# AVRI2CIO.net
KiCad netlist of a schematic drawn in EAGLE
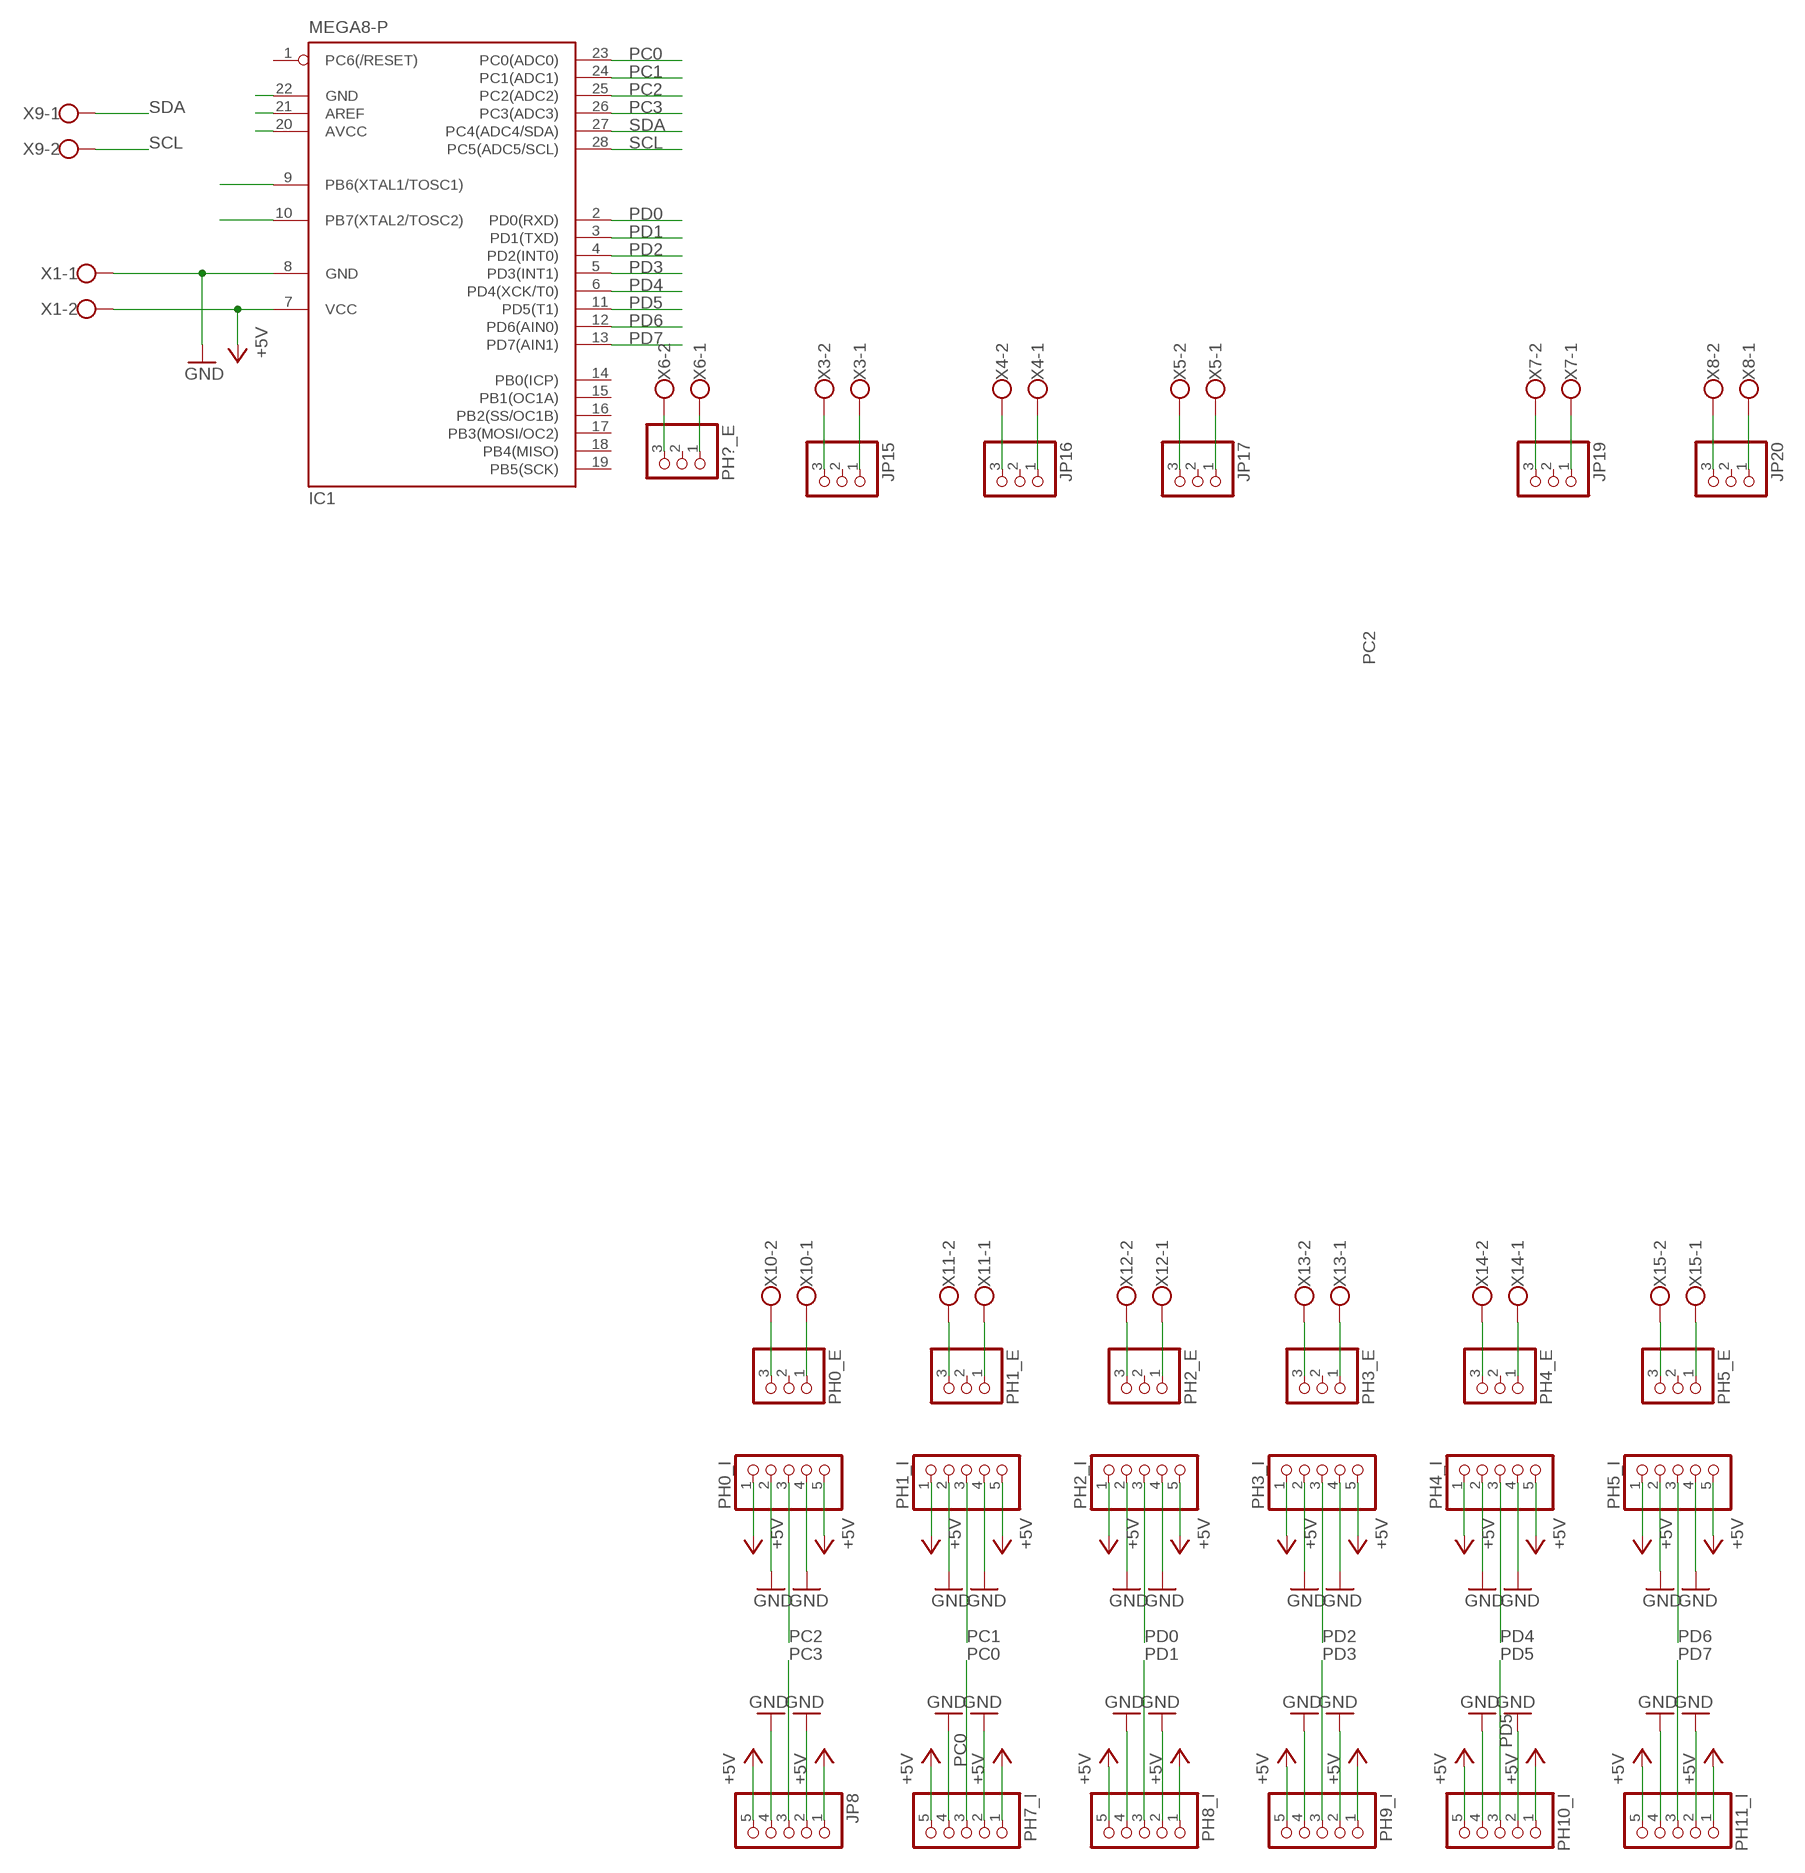
[diagram p0: schematic, sheet 1]

(export (version "E")
  (design (tool "Eeschema 10.0.6"))
  (components
    (comp (ref "IC1")
      (value "MEGA8-P")
      (footprint "eagle-import:DIL28-3")
      (libsource (lib "eagle-import") (part "MEGA8-P"))
    )
    (comp (ref "JP8")
      (value "PINHD-1X5")
      (footprint "eagle-import:1X05")
      (libsource (lib "eagle-import") (part "PINHD-1X5"))
    )
    (comp (ref "JP15")
      (value "PINHD-1X3")
      (footprint "eagle-import:1X03")
      (libsource (lib "eagle-import") (part "PINHD-1X3"))
    )
    (comp (ref "JP16")
      (value "PINHD-1X3")
      (footprint "eagle-import:1X03")
      (libsource (lib "eagle-import") (part "PINHD-1X3"))
    )
    (comp (ref "JP17")
      (value "PINHD-1X3")
      (footprint "eagle-import:1X03")
      (libsource (lib "eagle-import") (part "PINHD-1X3"))
    )
    (comp (ref "JP19")
      (value "PINHD-1X3")
      (footprint "eagle-import:1X03")
      (libsource (lib "eagle-import") (part "PINHD-1X3"))
    )
    (comp (ref "JP20")
      (value "PINHD-1X3")
      (footprint "eagle-import:1X03")
      (libsource (lib "eagle-import") (part "PINHD-1X3"))
    )
    (comp (ref "PH0_E")
      (value "PINHD-1X3")
      (footprint "eagle-import:1X03")
      (libsource (lib "eagle-import") (part "PINHD-1X3"))
    )
    (comp (ref "PH0_I")
      (value "PINHD-1X5")
      (footprint "eagle-import:1X05")
      (libsource (lib "eagle-import") (part "PINHD-1X5"))
    )
    (comp (ref "PH1_E")
      (value "PINHD-1X3")
      (footprint "eagle-import:1X03")
      (libsource (lib "eagle-import") (part "PINHD-1X3"))
    )
    (comp (ref "PH1_I")
      (value "PINHD-1X5")
      (footprint "eagle-import:1X05")
      (libsource (lib "eagle-import") (part "PINHD-1X5"))
    )
    (comp (ref "PH2_E")
      (value "PINHD-1X3")
      (footprint "eagle-import:1X03")
      (libsource (lib "eagle-import") (part "PINHD-1X3"))
    )
    (comp (ref "PH2_I")
      (value "PINHD-1X5")
      (footprint "eagle-import:1X05")
      (libsource (lib "eagle-import") (part "PINHD-1X5"))
    )
    (comp (ref "PH3_E")
      (value "PINHD-1X3")
      (footprint "eagle-import:1X03")
      (libsource (lib "eagle-import") (part "PINHD-1X3"))
    )
    (comp (ref "PH3_I")
      (value "PINHD-1X5")
      (footprint "eagle-import:1X05")
      (libsource (lib "eagle-import") (part "PINHD-1X5"))
    )
    (comp (ref "PH4_E")
      (value "PINHD-1X3")
      (footprint "eagle-import:1X03")
      (libsource (lib "eagle-import") (part "PINHD-1X3"))
    )
    (comp (ref "PH4_I")
      (value "PINHD-1X5")
      (footprint "eagle-import:1X05")
      (libsource (lib "eagle-import") (part "PINHD-1X5"))
    )
    (comp (ref "PH5_E")
      (value "PINHD-1X3")
      (footprint "eagle-import:1X03")
      (libsource (lib "eagle-import") (part "PINHD-1X3"))
    )
    (comp (ref "PH5_I")
      (value "PINHD-1X5")
      (footprint "eagle-import:1X05")
      (libsource (lib "eagle-import") (part "PINHD-1X5"))
    )
    (comp (ref "PH7_I")
      (value "PINHD-1X5")
      (footprint "eagle-import:1X05")
      (libsource (lib "eagle-import") (part "PINHD-1X5"))
    )
    (comp (ref "PH8_I")
      (value "PINHD-1X5")
      (footprint "eagle-import:1X05")
      (libsource (lib "eagle-import") (part "PINHD-1X5"))
    )
    (comp (ref "PH9_I")
      (value "PINHD-1X5")
      (footprint "eagle-import:1X05")
      (libsource (lib "eagle-import") (part "PINHD-1X5"))
    )
    (comp (ref "PH10_I")
      (value "PINHD-1X5")
      (footprint "eagle-import:1X05")
      (libsource (lib "eagle-import") (part "PINHD-1X5"))
    )
    (comp (ref "PH11_I")
      (value "PINHD-1X5")
      (footprint "eagle-import:1X05")
      (libsource (lib "eagle-import") (part "PINHD-1X5"))
    )
    (comp (ref "PH?_E")
      (value "PINHD-1X3")
      (footprint "eagle-import:1X03")
      (libsource (lib "eagle-import") (part "PINHD-1X3"))
    )
    (comp (ref "X1")
      (value "W237-102")
      (footprint "eagle-import:W237-102")
      (fields (field (name "MPN") "237-102"))
      (libsource (lib "eagle-import") (part "W237-102"))
    )
    (comp (ref "X3")
      (value "W237-102")
      (footprint "eagle-import:W237-102")
      (fields (field (name "MPN") "237-102"))
      (libsource (lib "eagle-import") (part "W237-102"))
    )
    (comp (ref "X4")
      (value "W237-102")
      (footprint "eagle-import:W237-102")
      (fields (field (name "MPN") "237-102"))
      (libsource (lib "eagle-import") (part "W237-102"))
    )
    (comp (ref "X5")
      (value "W237-102")
      (footprint "eagle-import:W237-102")
      (fields (field (name "MPN") "237-102"))
      (libsource (lib "eagle-import") (part "W237-102"))
    )
    (comp (ref "X6")
      (value "W237-102")
      (footprint "eagle-import:W237-102")
      (fields (field (name "MPN") "237-102"))
      (libsource (lib "eagle-import") (part "W237-102"))
    )
    (comp (ref "X7")
      (value "W237-102")
      (footprint "eagle-import:W237-102")
      (fields (field (name "MPN") "237-102"))
      (libsource (lib "eagle-import") (part "W237-102"))
    )
    (comp (ref "X8")
      (value "W237-102")
      (footprint "eagle-import:W237-102")
      (fields (field (name "MPN") "237-102"))
      (libsource (lib "eagle-import") (part "W237-102"))
    )
    (comp (ref "X9")
      (value "W237-102")
      (footprint "eagle-import:W237-102")
      (fields (field (name "MPN") "237-102"))
      (libsource (lib "eagle-import") (part "W237-102"))
    )
    (comp (ref "X10")
      (value "W237-102")
      (footprint "eagle-import:W237-102")
      (fields (field (name "MPN") "237-102"))
      (libsource (lib "eagle-import") (part "W237-102"))
    )
    (comp (ref "X11")
      (value "W237-102")
      (footprint "eagle-import:W237-102")
      (fields (field (name "MPN") "237-102"))
      (libsource (lib "eagle-import") (part "W237-102"))
    )
    (comp (ref "X12")
      (value "W237-102")
      (footprint "eagle-import:W237-102")
      (fields (field (name "MPN") "237-102"))
      (libsource (lib "eagle-import") (part "W237-102"))
    )
    (comp (ref "X13")
      (value "W237-102")
      (footprint "eagle-import:W237-102")
      (fields (field (name "MPN") "237-102"))
      (libsource (lib "eagle-import") (part "W237-102"))
    )
    (comp (ref "X14")
      (value "W237-102")
      (footprint "eagle-import:W237-102")
      (fields (field (name "MPN") "237-102"))
      (libsource (lib "eagle-import") (part "W237-102"))
    )
    (comp (ref "X15")
      (value "W237-102")
      (footprint "eagle-import:W237-102")
      (fields (field (name "MPN") "237-102"))
      (libsource (lib "eagle-import") (part "W237-102"))
    )
  )
  (nets
    (net (code "1") (name "+5V") (class "Default")
      (node (ref "IC1") (pin "7") (pinfunction "VCC_7") (pintype "power_in"))
      (node (ref "JP8") (pin "1") (pinfunction "1_1") (pintype "passive"))
      (node (ref "JP8") (pin "5") (pinfunction "5_5") (pintype "passive"))
      (node (ref "PH0_I") (pin "1") (pinfunction "1_1") (pintype "passive"))
      (node (ref "PH0_I") (pin "5") (pinfunction "5_5") (pintype "passive"))
      (node (ref "PH10_I") (pin "1") (pinfunction "1_1") (pintype "passive"))
      (node (ref "PH10_I") (pin "5") (pinfunction "5_5") (pintype "passive"))
      (node (ref "PH11_I") (pin "1") (pinfunction "1_1") (pintype "passive"))
      (node (ref "PH11_I") (pin "5") (pinfunction "5_5") (pintype "passive"))
      (node (ref "PH1_I") (pin "1") (pinfunction "1_1") (pintype "passive"))
      (node (ref "PH1_I") (pin "5") (pinfunction "5_5") (pintype "passive"))
      (node (ref "PH2_I") (pin "1") (pinfunction "1_1") (pintype "passive"))
      (node (ref "PH2_I") (pin "5") (pinfunction "5_5") (pintype "passive"))
      (node (ref "PH3_I") (pin "1") (pinfunction "1_1") (pintype "passive"))
      (node (ref "PH3_I") (pin "5") (pinfunction "5_5") (pintype "passive"))
      (node (ref "PH4_I") (pin "1") (pinfunction "1_1") (pintype "passive"))
      (node (ref "PH4_I") (pin "5") (pinfunction "5_5") (pintype "passive"))
      (node (ref "PH5_I") (pin "1") (pinfunction "1_1") (pintype "passive"))
      (node (ref "PH5_I") (pin "5") (pinfunction "5_5") (pintype "passive"))
      (node (ref "PH7_I") (pin "1") (pinfunction "1_1") (pintype "passive"))
      (node (ref "PH7_I") (pin "5") (pinfunction "5_5") (pintype "passive"))
      (node (ref "PH8_I") (pin "1") (pinfunction "1_1") (pintype "passive"))
      (node (ref "PH8_I") (pin "5") (pinfunction "5_5") (pintype "passive"))
      (node (ref "PH9_I") (pin "1") (pinfunction "1_1") (pintype "passive"))
      (node (ref "PH9_I") (pin "5") (pinfunction "5_5") (pintype "passive"))
      (node (ref "X1") (pin "2") (pinfunction "KL_2") (pintype "passive"))
    )
    (net (code "2") (name "/PC0") (class "Default")
      (node (ref "IC1") (pin "23") (pinfunction "PC0(ADC0)_23") (pintype "bidirectional"))
      (node (ref "PH7_I") (pin "3") (pinfunction "3_3") (pintype "passive"))
    )
    (net (code "3") (name "/PC1") (class "Default")
      (node (ref "IC1") (pin "24") (pinfunction "PC1(ADC1)_24") (pintype "bidirectional"))
      (node (ref "PH1_I") (pin "3") (pinfunction "3_3") (pintype "passive"))
    )
    (net (code "4") (name "/PC2") (class "Default")
      (node (ref "IC1") (pin "25") (pinfunction "PC2(ADC2)_25") (pintype "bidirectional"))
      (node (ref "PH0_I") (pin "3") (pinfunction "3_3") (pintype "passive"))
    )
    (net (code "5") (name "/PC3") (class "Default")
      (node (ref "IC1") (pin "26") (pinfunction "PC3(ADC3)_26") (pintype "bidirectional"))
      (node (ref "JP8") (pin "3") (pinfunction "3_3") (pintype "passive"))
    )
    (net (code "6") (name "/PD0") (class "Default")
      (node (ref "IC1") (pin "2") (pinfunction "PD0(RXD)_2") (pintype "bidirectional"))
      (node (ref "PH2_I") (pin "3") (pinfunction "3_3") (pintype "passive"))
    )
    (net (code "7") (name "/PD1") (class "Default")
      (node (ref "IC1") (pin "3") (pinfunction "PD1(TXD)_3") (pintype "bidirectional"))
      (node (ref "PH8_I") (pin "3") (pinfunction "3_3") (pintype "passive"))
    )
    (net (code "8") (name "/PD2") (class "Default")
      (node (ref "IC1") (pin "4") (pinfunction "PD2(INT0)_4") (pintype "bidirectional"))
      (node (ref "PH3_I") (pin "3") (pinfunction "3_3") (pintype "passive"))
    )
    (net (code "9") (name "/PD3") (class "Default")
      (node (ref "IC1") (pin "5") (pinfunction "PD3(INT1)_5") (pintype "bidirectional"))
      (node (ref "PH9_I") (pin "3") (pinfunction "3_3") (pintype "passive"))
    )
    (net (code "10") (name "/PD4") (class "Default")
      (node (ref "IC1") (pin "6") (pinfunction "PD4(XCK/T0)_6") (pintype "bidirectional"))
      (node (ref "PH4_I") (pin "3") (pinfunction "3_3") (pintype "passive"))
    )
    (net (code "11") (name "/PD5") (class "Default")
      (node (ref "IC1") (pin "11") (pinfunction "PD5(T1)_11") (pintype "bidirectional"))
      (node (ref "PH10_I") (pin "3") (pinfunction "3_3") (pintype "passive"))
    )
    (net (code "12") (name "/PD6") (class "Default")
      (node (ref "IC1") (pin "12") (pinfunction "PD6(AIN0)_12") (pintype "bidirectional"))
      (node (ref "PH5_I") (pin "3") (pinfunction "3_3") (pintype "passive"))
    )
    (net (code "13") (name "/PD7") (class "Default")
      (node (ref "IC1") (pin "13") (pinfunction "PD7(AIN1)_13") (pintype "bidirectional"))
      (node (ref "PH11_I") (pin "3") (pinfunction "3_3") (pintype "passive"))
    )
    (net (code "14") (name "/SCL") (class "Default")
      (node (ref "IC1") (pin "28") (pinfunction "PC5(ADC5/SCL)_28") (pintype "bidirectional"))
      (node (ref "X9") (pin "2") (pinfunction "KL_2") (pintype "passive"))
    )
    (net (code "15") (name "/SDA") (class "Default")
      (node (ref "IC1") (pin "27") (pinfunction "PC4(ADC4/SDA)_27") (pintype "bidirectional"))
      (node (ref "X9") (pin "1") (pinfunction "KL_1") (pintype "passive"))
    )
    (net (code "16") (name "GND") (class "Default")
      (node (ref "IC1") (pin "8") (pinfunction "GND_8") (pintype "power_in"))
      (node (ref "JP8") (pin "2") (pinfunction "2_2") (pintype "passive"))
      (node (ref "JP8") (pin "4") (pinfunction "4_4") (pintype "passive"))
      (node (ref "PH0_I") (pin "2") (pinfunction "2_2") (pintype "passive"))
      (node (ref "PH0_I") (pin "4") (pinfunction "4_4") (pintype "passive"))
      (node (ref "PH10_I") (pin "2") (pinfunction "2_2") (pintype "passive"))
      (node (ref "PH10_I") (pin "4") (pinfunction "4_4") (pintype "passive"))
      (node (ref "PH11_I") (pin "2") (pinfunction "2_2") (pintype "passive"))
      (node (ref "PH11_I") (pin "4") (pinfunction "4_4") (pintype "passive"))
      (node (ref "PH1_I") (pin "2") (pinfunction "2_2") (pintype "passive"))
      (node (ref "PH1_I") (pin "4") (pinfunction "4_4") (pintype "passive"))
      (node (ref "PH2_I") (pin "2") (pinfunction "2_2") (pintype "passive"))
      (node (ref "PH2_I") (pin "4") (pinfunction "4_4") (pintype "passive"))
      (node (ref "PH3_I") (pin "2") (pinfunction "2_2") (pintype "passive"))
      (node (ref "PH3_I") (pin "4") (pinfunction "4_4") (pintype "passive"))
      (node (ref "PH4_I") (pin "2") (pinfunction "2_2") (pintype "passive"))
      (node (ref "PH4_I") (pin "4") (pinfunction "4_4") (pintype "passive"))
      (node (ref "PH5_I") (pin "2") (pinfunction "2_2") (pintype "passive"))
      (node (ref "PH5_I") (pin "4") (pinfunction "4_4") (pintype "passive"))
      (node (ref "PH7_I") (pin "2") (pinfunction "2_2") (pintype "passive"))
      (node (ref "PH7_I") (pin "4") (pinfunction "4_4") (pintype "passive"))
      (node (ref "PH8_I") (pin "2") (pinfunction "2_2") (pintype "passive"))
      (node (ref "PH8_I") (pin "4") (pinfunction "4_4") (pintype "passive"))
      (node (ref "PH9_I") (pin "2") (pinfunction "2_2") (pintype "passive"))
      (node (ref "PH9_I") (pin "4") (pinfunction "4_4") (pintype "passive"))
      (node (ref "X1") (pin "1") (pinfunction "KL_1") (pintype "passive"))
    )
    (net (code "17") (name "Net-(X3A-KL)") (class "Default")
      (node (ref "JP15") (pin "1") (pinfunction "1_1") (pintype "passive"))
      (node (ref "X3") (pin "1") (pinfunction "KL_1") (pintype "passive"))
    )
    (net (code "18") (name "Net-(X3B-KL)") (class "Default")
      (node (ref "JP15") (pin "3") (pinfunction "3_3") (pintype "passive"))
      (node (ref "X3") (pin "2") (pinfunction "KL_2") (pintype "passive"))
    )
    (net (code "19") (name "Net-(X4A-KL)") (class "Default")
      (node (ref "JP16") (pin "1") (pinfunction "1_1") (pintype "passive"))
      (node (ref "X4") (pin "1") (pinfunction "KL_1") (pintype "passive"))
    )
    (net (code "20") (name "Net-(X4B-KL)") (class "Default")
      (node (ref "JP16") (pin "3") (pinfunction "3_3") (pintype "passive"))
      (node (ref "X4") (pin "2") (pinfunction "KL_2") (pintype "passive"))
    )
    (net (code "21") (name "Net-(X5A-KL)") (class "Default")
      (node (ref "JP17") (pin "1") (pinfunction "1_1") (pintype "passive"))
      (node (ref "X5") (pin "1") (pinfunction "KL_1") (pintype "passive"))
    )
    (net (code "22") (name "Net-(X5B-KL)") (class "Default")
      (node (ref "JP17") (pin "3") (pinfunction "3_3") (pintype "passive"))
      (node (ref "X5") (pin "2") (pinfunction "KL_2") (pintype "passive"))
    )
    (net (code "23") (name "Net-(X6A-KL)") (class "Default")
      (node (ref "PH?_E") (pin "1") (pinfunction "1_1") (pintype "passive"))
      (node (ref "X6") (pin "1") (pinfunction "KL_1") (pintype "passive"))
    )
    (net (code "24") (name "Net-(X6B-KL)") (class "Default")
      (node (ref "PH?_E") (pin "3") (pinfunction "3_3") (pintype "passive"))
      (node (ref "X6") (pin "2") (pinfunction "KL_2") (pintype "passive"))
    )
    (net (code "25") (name "Net-(X7A-KL)") (class "Default")
      (node (ref "JP19") (pin "1") (pinfunction "1_1") (pintype "passive"))
      (node (ref "X7") (pin "1") (pinfunction "KL_1") (pintype "passive"))
    )
    (net (code "26") (name "Net-(X7B-KL)") (class "Default")
      (node (ref "JP19") (pin "3") (pinfunction "3_3") (pintype "passive"))
      (node (ref "X7") (pin "2") (pinfunction "KL_2") (pintype "passive"))
    )
    (net (code "27") (name "Net-(X8A-KL)") (class "Default")
      (node (ref "JP20") (pin "1") (pinfunction "1_1") (pintype "passive"))
      (node (ref "X8") (pin "1") (pinfunction "KL_1") (pintype "passive"))
    )
    (net (code "28") (name "Net-(X8B-KL)") (class "Default")
      (node (ref "JP20") (pin "3") (pinfunction "3_3") (pintype "passive"))
      (node (ref "X8") (pin "2") (pinfunction "KL_2") (pintype "passive"))
    )
    (net (code "29") (name "Net-(X10A-KL)") (class "Default")
      (node (ref "PH0_E") (pin "1") (pinfunction "1_1") (pintype "passive"))
      (node (ref "X10") (pin "1") (pinfunction "KL_1") (pintype "passive"))
    )
    (net (code "30") (name "Net-(X10B-KL)") (class "Default")
      (node (ref "PH0_E") (pin "3") (pinfunction "3_3") (pintype "passive"))
      (node (ref "X10") (pin "2") (pinfunction "KL_2") (pintype "passive"))
    )
    (net (code "31") (name "Net-(X11A-KL)") (class "Default")
      (node (ref "PH1_E") (pin "1") (pinfunction "1_1") (pintype "passive"))
      (node (ref "X11") (pin "1") (pinfunction "KL_1") (pintype "passive"))
    )
    (net (code "32") (name "Net-(X11B-KL)") (class "Default")
      (node (ref "PH1_E") (pin "3") (pinfunction "3_3") (pintype "passive"))
      (node (ref "X11") (pin "2") (pinfunction "KL_2") (pintype "passive"))
    )
    (net (code "33") (name "Net-(X12A-KL)") (class "Default")
      (node (ref "PH2_E") (pin "1") (pinfunction "1_1") (pintype "passive"))
      (node (ref "X12") (pin "1") (pinfunction "KL_1") (pintype "passive"))
    )
    (net (code "34") (name "Net-(X12B-KL)") (class "Default")
      (node (ref "PH2_E") (pin "3") (pinfunction "3_3") (pintype "passive"))
      (node (ref "X12") (pin "2") (pinfunction "KL_2") (pintype "passive"))
    )
    (net (code "35") (name "Net-(X13A-KL)") (class "Default")
      (node (ref "PH3_E") (pin "1") (pinfunction "1_1") (pintype "passive"))
      (node (ref "X13") (pin "1") (pinfunction "KL_1") (pintype "passive"))
    )
    (net (code "36") (name "Net-(X13B-KL)") (class "Default")
      (node (ref "PH3_E") (pin "3") (pinfunction "3_3") (pintype "passive"))
      (node (ref "X13") (pin "2") (pinfunction "KL_2") (pintype "passive"))
    )
    (net (code "37") (name "Net-(X14A-KL)") (class "Default")
      (node (ref "PH4_E") (pin "1") (pinfunction "1_1") (pintype "passive"))
      (node (ref "X14") (pin "1") (pinfunction "KL_1") (pintype "passive"))
    )
    (net (code "38") (name "Net-(X14B-KL)") (class "Default")
      (node (ref "PH4_E") (pin "3") (pinfunction "3_3") (pintype "passive"))
      (node (ref "X14") (pin "2") (pinfunction "KL_2") (pintype "passive"))
    )
    (net (code "39") (name "Net-(X15A-KL)") (class "Default")
      (node (ref "PH5_E") (pin "1") (pinfunction "1_1") (pintype "passive"))
      (node (ref "X15") (pin "1") (pinfunction "KL_1") (pintype "passive"))
    )
    (net (code "40") (name "Net-(X15B-KL)") (class "Default")
      (node (ref "PH5_E") (pin "3") (pinfunction "3_3") (pintype "passive"))
      (node (ref "X15") (pin "2") (pinfunction "KL_2") (pintype "passive"))
    )
    (net (code "41") (name "unconnected-(IC1-AREF-Pad21)") (class "Default")
      (node (ref "IC1") (pin "21") (pinfunction "AREF_21") (pintype "passive"))
    )
    (net (code "42") (name "unconnected-(IC1-AVCC-Pad20)") (class "Default")
      (node (ref "IC1") (pin "20") (pinfunction "AVCC_20") (pintype "power_in"))
    )
    (net (code "43") (name "unconnected-(IC1-GND-Pad22)") (class "Default")
      (node (ref "IC1") (pin "22") (pinfunction "GND_22") (pintype "power_in"))
    )
    (net (code "44") (name "unconnected-(IC1-PB0(ICP)-Pad14)") (class "Default")
      (node (ref "IC1") (pin "14") (pinfunction "PB0(ICP)_14") (pintype "bidirectional"))
    )
    (net (code "45") (name "unconnected-(IC1-PB1(OC1A)-Pad15)") (class "Default")
      (node (ref "IC1") (pin "15") (pinfunction "PB1(OC1A)_15") (pintype "bidirectional"))
    )
    (net (code "46") (name "unconnected-(IC1-PB2(SS{slash}OC1B)-Pad16)") (class "Default")
      (node (ref "IC1") (pin "16") (pinfunction "PB2(SS/OC1B)_16") (pintype "bidirectional"))
    )
    (net (code "47") (name "unconnected-(IC1-PB3(MOSI{slash}OC2)-Pad17)") (class "Default")
      (node (ref "IC1") (pin "17") (pinfunction "PB3(MOSI/OC2)_17") (pintype "bidirectional"))
    )
    (net (code "48") (name "unconnected-(IC1-PB4(MISO)-Pad18)") (class "Default")
      (node (ref "IC1") (pin "18") (pinfunction "PB4(MISO)_18") (pintype "bidirectional"))
    )
    (net (code "49") (name "unconnected-(IC1-PB5(SCK)-Pad19)") (class "Default")
      (node (ref "IC1") (pin "19") (pinfunction "PB5(SCK)_19") (pintype "bidirectional"))
    )
    (net (code "50") (name "unconnected-(IC1-PB6(XTAL1{slash}TOSC1)-Pad9)") (class "Default")
      (node (ref "IC1") (pin "9") (pinfunction "PB6(XTAL1/TOSC1)_9") (pintype "bidirectional"))
    )
    (net (code "51") (name "unconnected-(IC1-PB7(XTAL2{slash}TOSC2)-Pad10)") (class "Default")
      (node (ref "IC1") (pin "10") (pinfunction "PB7(XTAL2/TOSC2)_10") (pintype "bidirectional"))
    )
    (net (code "52") (name "unconnected-(IC1-PC6({slash}RESET)-Pad1)") (class "Default")
      (node (ref "IC1") (pin "1") (pinfunction "PC6(/RESET)_1") (pintype "bidirectional"))
    )
    (net (code "53") (name "unconnected-(JP15-Pad2)") (class "Default")
      (node (ref "JP15") (pin "2") (pinfunction "2_2") (pintype "passive"))
    )
    (net (code "54") (name "unconnected-(JP16-Pad2)") (class "Default")
      (node (ref "JP16") (pin "2") (pinfunction "2_2") (pintype "passive"))
    )
    (net (code "55") (name "unconnected-(JP17-Pad2)") (class "Default")
      (node (ref "JP17") (pin "2") (pinfunction "2_2") (pintype "passive"))
    )
    (net (code "56") (name "unconnected-(JP19-Pad2)") (class "Default")
      (node (ref "JP19") (pin "2") (pinfunction "2_2") (pintype "passive"))
    )
    (net (code "57") (name "unconnected-(JP20-Pad2)") (class "Default")
      (node (ref "JP20") (pin "2") (pinfunction "2_2") (pintype "passive"))
    )
    (net (code "58") (name "unconnected-(PH0_E-Pad2)") (class "Default")
      (node (ref "PH0_E") (pin "2") (pinfunction "2_2") (pintype "passive"))
    )
    (net (code "59") (name "unconnected-(PH1_E-Pad2)") (class "Default")
      (node (ref "PH1_E") (pin "2") (pinfunction "2_2") (pintype "passive"))
    )
    (net (code "60") (name "unconnected-(PH2_E-Pad2)") (class "Default")
      (node (ref "PH2_E") (pin "2") (pinfunction "2_2") (pintype "passive"))
    )
    (net (code "61") (name "unconnected-(PH3_E-Pad2)") (class "Default")
      (node (ref "PH3_E") (pin "2") (pinfunction "2_2") (pintype "passive"))
    )
    (net (code "62") (name "unconnected-(PH4_E-Pad2)") (class "Default")
      (node (ref "PH4_E") (pin "2") (pinfunction "2_2") (pintype "passive"))
    )
    (net (code "63") (name "unconnected-(PH5_E-Pad2)") (class "Default")
      (node (ref "PH5_E") (pin "2") (pinfunction "2_2") (pintype "passive"))
    )
    (net (code "64") (name "unconnected-(PH?_E-Pad2)") (class "Default")
      (node (ref "PH?_E") (pin "2") (pinfunction "2_2") (pintype "passive"))
    )
  )
)
